# untitled.net
KiCad netlist of a schematic drawn in EAGLE
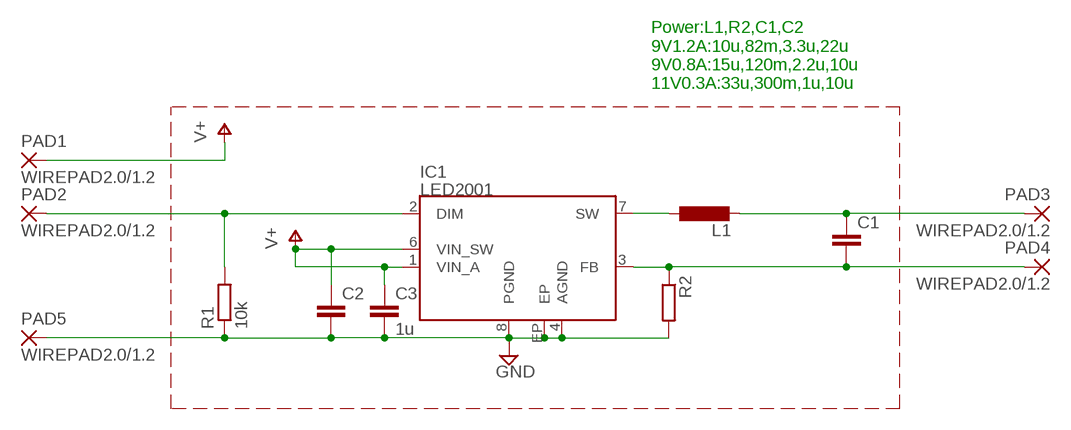
[diagram p0: schematic, sheet 1]

(export (version "E")
  (design (tool "Eeschema 10.0.6"))
  (components
    (comp (ref "C1")
      (value "C-EUC1210")
      (footprint "eagle-import:C1210")
      (libsource (lib "eagle-import") (part "C-EUC1210"))
    )
    (comp (ref "C2")
      (value "C-EUC0805")
      (footprint "eagle-import:C0805")
      (libsource (lib "eagle-import") (part "C-EUC0805"))
    )
    (comp (ref "C3")
      (value "1u")
      (footprint "eagle-import:C0603")
      (libsource (lib "eagle-import") (part "C-EUC0603"))
    )
    (comp (ref "IC1")
      (value "LED2001")
      (footprint "eagle-import:HSOP8")
      (libsource (lib "eagle-import") (part "LED2001"))
    )
    (comp (ref "L1")
      (value "L-EUL8080")
      (footprint "eagle-import:L8080")
      (libsource (lib "eagle-import") (part "L-EUL8080"))
    )
    (comp (ref "PAD1")
      (value "WIREPAD2.0/1.2")
      (footprint "eagle-import:2.0_1.3")
      (libsource (lib "eagle-import") (part "WIREPAD2.0/1.2"))
    )
    (comp (ref "PAD2")
      (value "WIREPAD2.0/1.2")
      (footprint "eagle-import:2.0_1.3")
      (libsource (lib "eagle-import") (part "WIREPAD2.0/1.2"))
    )
    (comp (ref "PAD3")
      (value "WIREPAD2.0/1.2")
      (footprint "eagle-import:2.0_1.3")
      (libsource (lib "eagle-import") (part "WIREPAD2.0/1.2"))
    )
    (comp (ref "PAD4")
      (value "WIREPAD2.0/1.2")
      (footprint "eagle-import:2.0_1.3")
      (libsource (lib "eagle-import") (part "WIREPAD2.0/1.2"))
    )
    (comp (ref "PAD5")
      (value "WIREPAD2.0/1.2")
      (footprint "eagle-import:2.0_1.3")
      (libsource (lib "eagle-import") (part "WIREPAD2.0/1.2"))
    )
    (comp (ref "R1")
      (value "10k")
      (footprint "eagle-import:R0402")
      (libsource (lib "eagle-import") (part "R-EU_R0402"))
    )
    (comp (ref "R2")
      (value "R-EU_R1210")
      (footprint "eagle-import:R1210")
      (libsource (lib "eagle-import") (part "R-EU_R1210"))
    )
  )
  (nets
    (net (code "1") (name "GND") (class "Default")
      (node (ref "C2") (pin "2") (pinfunction "2_2") (pintype "passive"))
      (node (ref "C3") (pin "2") (pinfunction "2_2") (pintype "passive"))
      (node (ref "IC1") (pin "4") (pinfunction "AGND_4") (pintype "power_in"))
      (node (ref "IC1") (pin "8") (pinfunction "PGND_8") (pintype "power_in"))
      (node (ref "IC1") (pin "EP") (pinfunction "EP_EP") (pintype "passive"))
      (node (ref "PAD5") (pin "1") (pinfunction "P_1") (pintype "passive"))
      (node (ref "R1") (pin "1") (pinfunction "1_1") (pintype "passive"))
      (node (ref "R2") (pin "2") (pinfunction "2_2") (pintype "passive"))
    )
    (net (code "2") (name "Net-(IC1-DIM)") (class "Default")
      (node (ref "IC1") (pin "2") (pinfunction "DIM_2") (pintype "input"))
      (node (ref "PAD2") (pin "1") (pinfunction "P_1") (pintype "passive"))
      (node (ref "R1") (pin "2") (pinfunction "2_2") (pintype "passive"))
    )
    (net (code "3") (name "Net-(IC1-FB)") (class "Default")
      (node (ref "C1") (pin "2") (pinfunction "2_2") (pintype "passive"))
      (node (ref "IC1") (pin "3") (pinfunction "FB_3") (pintype "input"))
      (node (ref "PAD4") (pin "1") (pinfunction "P_1") (pintype "passive"))
      (node (ref "R2") (pin "1") (pinfunction "1_1") (pintype "passive"))
    )
    (net (code "4") (name "Net-(IC1-SW)") (class "Default")
      (node (ref "IC1") (pin "7") (pinfunction "SW_7") (pintype "output"))
      (node (ref "L1") (pin "1") (pinfunction "1_1") (pintype "passive"))
    )
    (net (code "5") (name "Net-(PAD3-P)") (class "Default")
      (node (ref "C1") (pin "1") (pinfunction "1_1") (pintype "passive"))
      (node (ref "L1") (pin "2") (pinfunction "2_2") (pintype "passive"))
      (node (ref "PAD3") (pin "1") (pinfunction "P_1") (pintype "passive"))
    )
    (net (code "6") (name "V+") (class "Default")
      (node (ref "C2") (pin "1") (pinfunction "1_1") (pintype "passive"))
      (node (ref "C3") (pin "1") (pinfunction "1_1") (pintype "passive"))
      (node (ref "IC1") (pin "1") (pinfunction "VIN_A_1") (pintype "power_in"))
      (node (ref "IC1") (pin "6") (pinfunction "VIN_SW_6") (pintype "power_in"))
      (node (ref "PAD1") (pin "1") (pinfunction "P_1") (pintype "passive"))
    )
  )
)
